# HID-Bridge-ATmega_proto.net
KiCad netlist of a schematic drawn in EAGLE
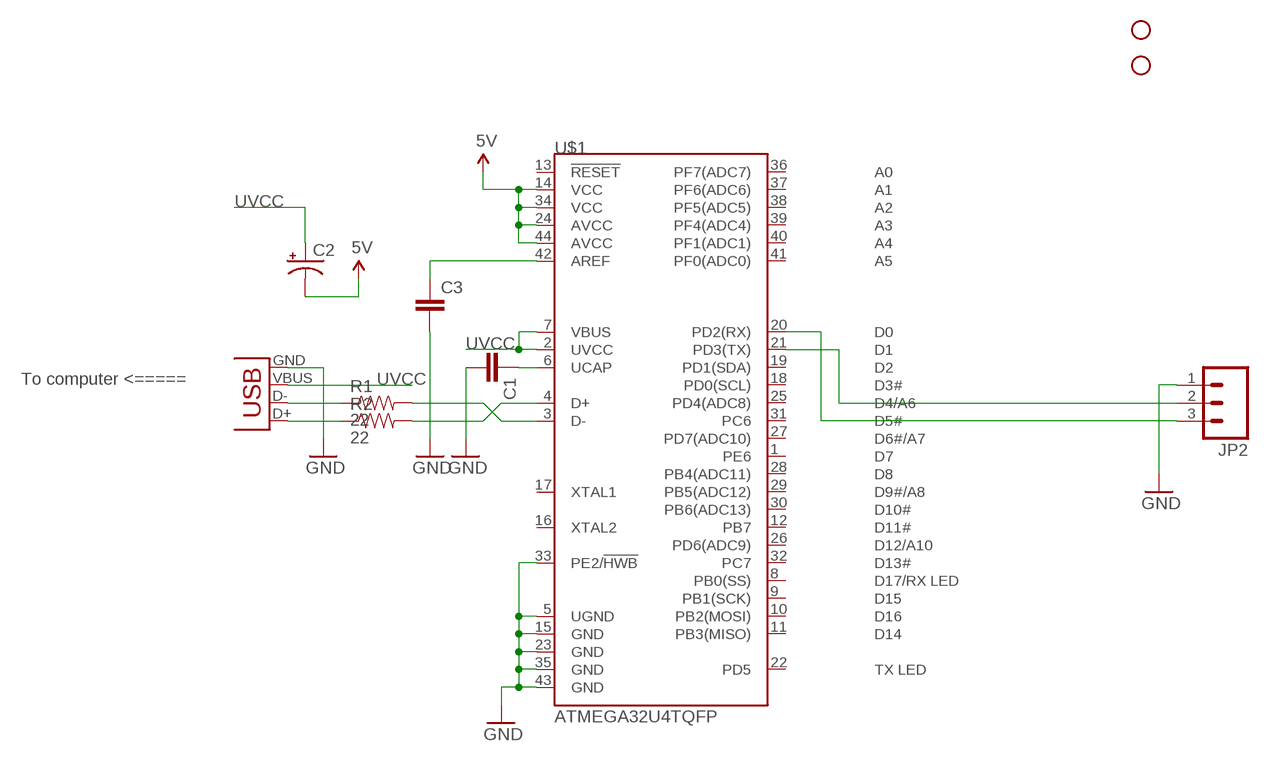
[diagram p0: schematic, sheet 1]

(export (version "E")
  (design (tool "Eeschema 10.0.6"))
  (components
    (comp (ref "C1")
      (value "CAPPTH")
      (footprint "eagle-import:CAP-PTH-SMALL")
      (libsource (lib "eagle-import") (part "CAPPTH"))
    )
    (comp (ref "C2")
      (value "10UF-25V-20%(PTH)")
      (footprint "eagle-import:CPOL-RADIAL-10UF-25V")
      (libsource (lib "eagle-import") (part "10UF-25V-20%(PTH)"))
    )
    (comp (ref "C3")
      (value "CAPPTH")
      (footprint "eagle-import:CAP-PTH-SMALL")
      (libsource (lib "eagle-import") (part "CAPPTH"))
    )
    (comp (ref "JP1")
      (value "USB-B")
      (footprint "eagle-import:USB-B-PTH")
      (libsource (lib "eagle-import") (part "USBPTH"))
    )
    (comp (ref "JP2")
      (value "M03PTH")
      (footprint "eagle-import:1X03")
      (libsource (lib "eagle-import") (part "M03PTH"))
    )
    (comp (ref "R1")
      (value "22")
      (footprint "eagle-import:AXIAL-0.1")
      (libsource (lib "eagle-import") (part "RESISTORPTH-1/4W-VERT"))
    )
    (comp (ref "R2")
      (value "22")
      (footprint "eagle-import:AXIAL-0.1")
      (libsource (lib "eagle-import") (part "RESISTORPTH-1/4W-VERT"))
    )
    (comp (ref "STANDOFF1")
      (value "STAND-OFF")
      (footprint "eagle-import:STAND-OFF")
      (libsource (lib "eagle-import") (part "STAND-OFF"))
    )
    (comp (ref "STANDOFF2")
      (value "STAND-OFF")
      (footprint "eagle-import:STAND-OFF")
      (libsource (lib "eagle-import") (part "STAND-OFF"))
    )
    (comp (ref "U$1")
      (value "ATMEGA32U4TQFP")
      (footprint "eagle-import:SPARKFUN-DIGITALIC_TQFP44")
      (libsource (lib "eagle-import") (part "ATMEGA32U4TQFP"))
    )
  )
  (nets
    (net (code "1") (name "/UVCC") (class "Default")
      (node (ref "C2") (pin "1") (pinfunction "+_1") (pintype "passive"))
      (node (ref "JP1") (pin "VBUS") (pinfunction "VBUS_VBUS") (pintype "bidirectional"))
      (node (ref "U$1") (pin "2") (pinfunction "UVCC_2") (pintype "bidirectional"))
      (node (ref "U$1") (pin "7") (pinfunction "VBUS_7") (pintype "bidirectional"))
    )
    (net (code "2") (name "5V") (class "Default")
      (node (ref "C2") (pin "2") (pinfunction "-_2") (pintype "passive"))
      (node (ref "U$1") (pin "14") (pinfunction "VCC_14") (pintype "bidirectional"))
      (node (ref "U$1") (pin "24") (pinfunction "AVCC_24") (pintype "bidirectional"))
      (node (ref "U$1") (pin "34") (pinfunction "VCC_34") (pintype "bidirectional"))
      (node (ref "U$1") (pin "44") (pinfunction "AVCC_44") (pintype "bidirectional"))
    )
    (net (code "3") (name "GND") (class "Default")
      (node (ref "C1") (pin "2") (pinfunction "2_2") (pintype "passive"))
      (node (ref "C3") (pin "2") (pinfunction "2_2") (pintype "passive"))
      (node (ref "JP1") (pin "GND") (pinfunction "GND_GND") (pintype "bidirectional"))
      (node (ref "JP2") (pin "1") (pinfunction "1_1") (pintype "passive"))
      (node (ref "U$1") (pin "15") (pinfunction "GND_15") (pintype "bidirectional"))
      (node (ref "U$1") (pin "23") (pinfunction "GND_23") (pintype "bidirectional"))
      (node (ref "U$1") (pin "33") (pinfunction "PE2/~{HWB}_33") (pintype "bidirectional"))
      (node (ref "U$1") (pin "35") (pinfunction "GND_35") (pintype "bidirectional"))
      (node (ref "U$1") (pin "43") (pinfunction "GND_43") (pintype "bidirectional"))
      (node (ref "U$1") (pin "5") (pinfunction "UGND_5") (pintype "bidirectional"))
    )
    (net (code "4") (name "Net-(R1-1)") (class "Default")
      (node (ref "JP1") (pin "D-") (pinfunction "D-_D-") (pintype "bidirectional"))
      (node (ref "R1") (pin "P$1") (pinfunction "1_P$1") (pintype "passive"))
    )
    (net (code "5") (name "Net-(R1-2)") (class "Default")
      (node (ref "R1") (pin "P$2") (pinfunction "2_P$2") (pintype "passive"))
      (node (ref "U$1") (pin "3") (pinfunction "D-_3") (pintype "bidirectional"))
    )
    (net (code "6") (name "Net-(R2-1)") (class "Default")
      (node (ref "JP1") (pin "D+") (pinfunction "D+_D+") (pintype "bidirectional"))
      (node (ref "R2") (pin "P$1") (pinfunction "1_P$1") (pintype "passive"))
    )
    (net (code "7") (name "Net-(R2-2)") (class "Default")
      (node (ref "R2") (pin "P$2") (pinfunction "2_P$2") (pintype "passive"))
      (node (ref "U$1") (pin "4") (pinfunction "D+_4") (pintype "bidirectional"))
    )
    (net (code "8") (name "Net-(U$1-AREF)") (class "Default")
      (node (ref "C3") (pin "1") (pinfunction "1_1") (pintype "passive"))
      (node (ref "U$1") (pin "42") (pinfunction "AREF_42") (pintype "bidirectional"))
    )
    (net (code "9") (name "Net-(U$1-PD2(RX))") (class "Default")
      (node (ref "JP2") (pin "3") (pinfunction "3_3") (pintype "passive"))
      (node (ref "U$1") (pin "20") (pinfunction "PD2(RX)_20") (pintype "bidirectional"))
    )
    (net (code "10") (name "Net-(U$1-PD3(TX))") (class "Default")
      (node (ref "JP2") (pin "2") (pinfunction "2_2") (pintype "passive"))
      (node (ref "U$1") (pin "21") (pinfunction "PD3(TX)_21") (pintype "bidirectional"))
    )
    (net (code "11") (name "Net-(U$1-UCAP)") (class "Default")
      (node (ref "C1") (pin "1") (pinfunction "1_1") (pintype "passive"))
      (node (ref "U$1") (pin "6") (pinfunction "UCAP_6") (pintype "bidirectional"))
    )
    (net (code "12") (name "unconnected-(U$1-PB0(SS)-Pad8)") (class "Default")
      (node (ref "U$1") (pin "8") (pinfunction "PB0(SS)_8") (pintype "bidirectional"))
    )
    (net (code "13") (name "unconnected-(U$1-PB1(SCK)-Pad9)") (class "Default")
      (node (ref "U$1") (pin "9") (pinfunction "PB1(SCK)_9") (pintype "bidirectional"))
    )
    (net (code "14") (name "unconnected-(U$1-PB2(MOSI)-Pad10)") (class "Default")
      (node (ref "U$1") (pin "10") (pinfunction "PB2(MOSI)_10") (pintype "bidirectional"))
    )
    (net (code "15") (name "unconnected-(U$1-PB3(MISO)-Pad11)") (class "Default")
      (node (ref "U$1") (pin "11") (pinfunction "PB3(MISO)_11") (pintype "bidirectional"))
    )
    (net (code "16") (name "unconnected-(U$1-PB4(ADC11)-Pad28)") (class "Default")
      (node (ref "U$1") (pin "28") (pinfunction "PB4(ADC11)_28") (pintype "bidirectional"))
    )
    (net (code "17") (name "unconnected-(U$1-PB5(ADC12)-Pad29)") (class "Default")
      (node (ref "U$1") (pin "29") (pinfunction "PB5(ADC12)_29") (pintype "bidirectional"))
    )
    (net (code "18") (name "unconnected-(U$1-PB6(ADC13)-Pad30)") (class "Default")
      (node (ref "U$1") (pin "30") (pinfunction "PB6(ADC13)_30") (pintype "bidirectional"))
    )
    (net (code "19") (name "unconnected-(U$1-PB7-Pad12)") (class "Default")
      (node (ref "U$1") (pin "12") (pinfunction "PB7_12") (pintype "bidirectional"))
    )
    (net (code "20") (name "unconnected-(U$1-PC6-Pad31)") (class "Default")
      (node (ref "U$1") (pin "31") (pinfunction "PC6_31") (pintype "bidirectional"))
    )
    (net (code "21") (name "unconnected-(U$1-PC7-Pad32)") (class "Default")
      (node (ref "U$1") (pin "32") (pinfunction "PC7_32") (pintype "bidirectional"))
    )
    (net (code "22") (name "unconnected-(U$1-PD0(SCL)-Pad18)") (class "Default")
      (node (ref "U$1") (pin "18") (pinfunction "PD0(SCL)_18") (pintype "bidirectional"))
    )
    (net (code "23") (name "unconnected-(U$1-PD1(SDA)-Pad19)") (class "Default")
      (node (ref "U$1") (pin "19") (pinfunction "PD1(SDA)_19") (pintype "bidirectional"))
    )
    (net (code "24") (name "unconnected-(U$1-PD4(ADC8)-Pad25)") (class "Default")
      (node (ref "U$1") (pin "25") (pinfunction "PD4(ADC8)_25") (pintype "bidirectional"))
    )
    (net (code "25") (name "unconnected-(U$1-PD5-Pad22)") (class "Default")
      (node (ref "U$1") (pin "22") (pinfunction "PD5_22") (pintype "bidirectional"))
    )
    (net (code "26") (name "unconnected-(U$1-PD6(ADC9)-Pad26)") (class "Default")
      (node (ref "U$1") (pin "26") (pinfunction "PD6(ADC9)_26") (pintype "bidirectional"))
    )
    (net (code "27") (name "unconnected-(U$1-PD7(ADC10)-Pad27)") (class "Default")
      (node (ref "U$1") (pin "27") (pinfunction "PD7(ADC10)_27") (pintype "bidirectional"))
    )
    (net (code "28") (name "unconnected-(U$1-PE6-Pad1)") (class "Default")
      (node (ref "U$1") (pin "1") (pinfunction "PE6_1") (pintype "bidirectional"))
    )
    (net (code "29") (name "unconnected-(U$1-PF0(ADC0)-Pad41)") (class "Default")
      (node (ref "U$1") (pin "41") (pinfunction "PF0(ADC0)_41") (pintype "bidirectional"))
    )
    (net (code "30") (name "unconnected-(U$1-PF1(ADC1)-Pad40)") (class "Default")
      (node (ref "U$1") (pin "40") (pinfunction "PF1(ADC1)_40") (pintype "bidirectional"))
    )
    (net (code "31") (name "unconnected-(U$1-PF4(ADC4)-Pad39)") (class "Default")
      (node (ref "U$1") (pin "39") (pinfunction "PF4(ADC4)_39") (pintype "bidirectional"))
    )
    (net (code "32") (name "unconnected-(U$1-PF5(ADC5)-Pad38)") (class "Default")
      (node (ref "U$1") (pin "38") (pinfunction "PF5(ADC5)_38") (pintype "bidirectional"))
    )
    (net (code "33") (name "unconnected-(U$1-PF6(ADC6)-Pad37)") (class "Default")
      (node (ref "U$1") (pin "37") (pinfunction "PF6(ADC6)_37") (pintype "bidirectional"))
    )
    (net (code "34") (name "unconnected-(U$1-PF7(ADC7)-Pad36)") (class "Default")
      (node (ref "U$1") (pin "36") (pinfunction "PF7(ADC7)_36") (pintype "bidirectional"))
    )
    (net (code "35") (name "unconnected-(U$1-XTAL1-Pad17)") (class "Default")
      (node (ref "U$1") (pin "17") (pinfunction "XTAL1_17") (pintype "bidirectional"))
    )
    (net (code "36") (name "unconnected-(U$1-XTAL2-Pad16)") (class "Default")
      (node (ref "U$1") (pin "16") (pinfunction "XTAL2_16") (pintype "bidirectional"))
    )
    (net (code "37") (name "unconnected-(U$1-~{RESET}-Pad13)") (class "Default")
      (node (ref "U$1") (pin "13") (pinfunction "~{RESET}_13") (pintype "bidirectional"))
    )
  )
)
